# 15_SOLEDNOID.net
KiCad netlist of a schematic drawn in Altium Designer
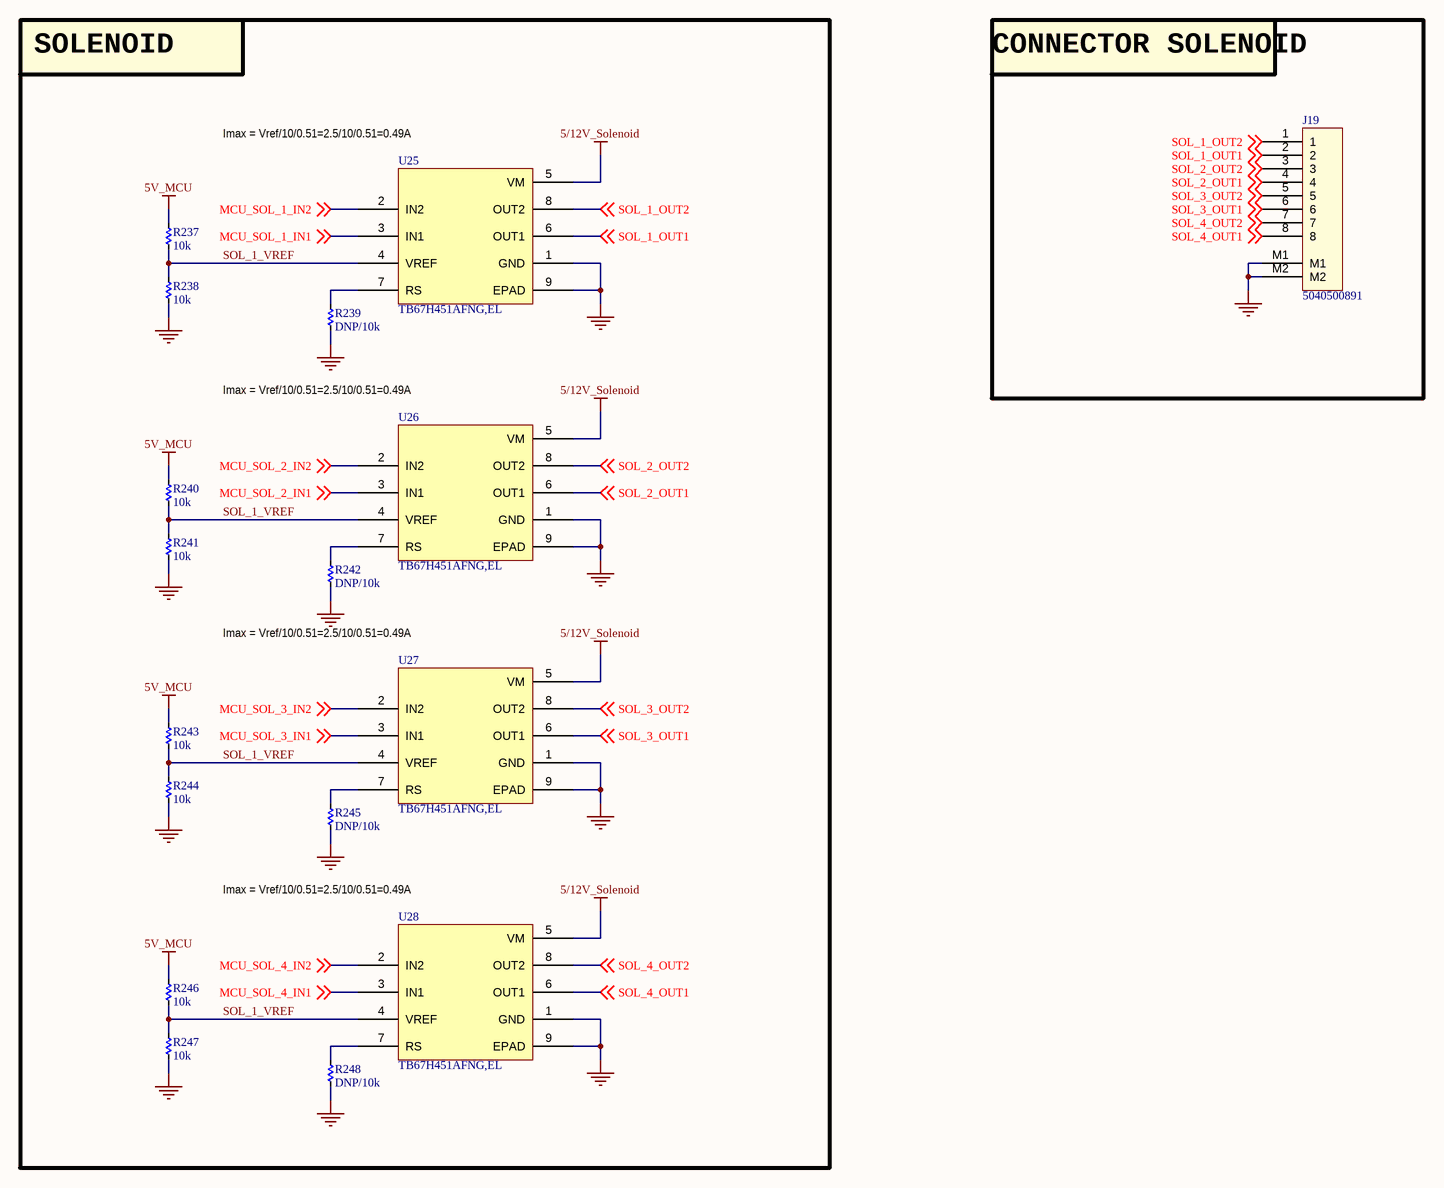
[diagram p0: 15_SOLEDNOID.SchDoc]

(export (version "E")
  (design (tool "Eeschema 10.0.6"))
  (components
    (comp (ref "J19")
      (value "5040500891")
      (footprint "MOLEX_5040500891")
      (libsource (lib "LABLIB") (part "Header 8x1_2M"))
    )
    (comp (ref "R237")
      (value "10k")
      (footprint "RES_C_1005X40")
      (description "RES")
      (libsource (lib "LABLIB") (part "_RES_B_2"))
    )
    (comp (ref "R238")
      (value "10k")
      (footprint "RES_C_1005X40")
      (description "RES")
      (libsource (lib "LABLIB") (part "_RES_B_2"))
    )
    (comp (ref "R239")
      (value "DNP/10k")
      (footprint "RES_C_1005X40")
      (description "RES")
      (libsource (lib "LABLIB") (part "_RES_B_2"))
    )
    (comp (ref "R240")
      (value "10k")
      (footprint "RES_C_1005X40")
      (description "RES")
      (libsource (lib "LABLIB") (part "_RES_B_2"))
    )
    (comp (ref "R241")
      (value "10k")
      (footprint "RES_C_1005X40")
      (description "RES")
      (libsource (lib "LABLIB") (part "_RES_B_2"))
    )
    (comp (ref "R242")
      (value "DNP/10k")
      (footprint "RES_C_1005X40")
      (description "RES")
      (libsource (lib "LABLIB") (part "_RES_B_2"))
    )
    (comp (ref "R243")
      (value "10k")
      (footprint "RES_C_1005X40")
      (description "RES")
      (libsource (lib "LABLIB") (part "_RES_B_2"))
    )
    (comp (ref "R244")
      (value "10k")
      (footprint "RES_C_1005X40")
      (description "RES")
      (libsource (lib "LABLIB") (part "_RES_B_2"))
    )
    (comp (ref "R245")
      (value "DNP/10k")
      (footprint "RES_C_1005X40")
      (description "RES")
      (libsource (lib "LABLIB") (part "_RES_B_2"))
    )
    (comp (ref "R246")
      (value "10k")
      (footprint "RES_C_1005X40")
      (description "RES")
      (libsource (lib "LABLIB") (part "_RES_B_2"))
    )
    (comp (ref "R247")
      (value "10k")
      (footprint "RES_C_1005X40")
      (description "RES")
      (libsource (lib "LABLIB") (part "_RES_B_2"))
    )
    (comp (ref "R248")
      (value "DNP/10k")
      (footprint "RES_C_1005X40")
      (description "RES")
      (libsource (lib "LABLIB") (part "_RES_B_2"))
    )
    (comp (ref "U25")
      (value "TB67H451AFNG,EL")
      (description "BRUSHED MOTOR DRIVER IC, 50V, 3.")
      (libsource (lib "LABLIB") (part "IC_H_bridge_TB67H451AFNG,EL"))
    )
    (comp (ref "U26")
      (value "TB67H451AFNG,EL")
      (description "BRUSHED MOTOR DRIVER IC, 50V, 3.")
      (libsource (lib "LABLIB") (part "IC_H_bridge_TB67H451AFNG,EL"))
    )
    (comp (ref "U27")
      (value "TB67H451AFNG,EL")
      (description "BRUSHED MOTOR DRIVER IC, 50V, 3.")
      (libsource (lib "LABLIB") (part "IC_H_bridge_TB67H451AFNG,EL"))
    )
    (comp (ref "U28")
      (value "TB67H451AFNG,EL")
      (description "BRUSHED MOTOR DRIVER IC, 50V, 3.")
      (libsource (lib "LABLIB") (part "IC_H_bridge_TB67H451AFNG,EL"))
    )
  )
  (nets
    (net (code "1") (name "/SOL_1_VREF") (class "Default")
      (node (ref "R237") (pin "2") (pinfunction "2_2") (pintype "passive"))
      (node (ref "R238") (pin "1") (pinfunction "1_1") (pintype "passive"))
      (node (ref "R240") (pin "2") (pinfunction "2_2") (pintype "passive"))
      (node (ref "R241") (pin "1") (pinfunction "1_1") (pintype "passive"))
      (node (ref "R243") (pin "2") (pinfunction "2_2") (pintype "passive"))
      (node (ref "R244") (pin "1") (pinfunction "1_1") (pintype "passive"))
      (node (ref "R246") (pin "2") (pinfunction "2_2") (pintype "passive"))
      (node (ref "R247") (pin "1") (pinfunction "1_1") (pintype "passive"))
      (node (ref "U25") (pin "4") (pinfunction "VREF_4") (pintype "passive"))
      (node (ref "U26") (pin "4") (pinfunction "VREF_4") (pintype "passive"))
      (node (ref "U27") (pin "4") (pinfunction "VREF_4") (pintype "passive"))
      (node (ref "U28") (pin "4") (pinfunction "VREF_4") (pintype "passive"))
    )
    (net (code "2") (name "5V_MCU") (class "Default")
      (node (ref "R237") (pin "1") (pinfunction "1_1") (pintype "passive"))
      (node (ref "R240") (pin "1") (pinfunction "1_1") (pintype "passive"))
      (node (ref "R243") (pin "1") (pinfunction "1_1") (pintype "passive"))
      (node (ref "R246") (pin "1") (pinfunction "1_1") (pintype "passive"))
    )
    (net (code "3") (name "5{slash}12V_Solenoid") (class "Default")
      (node (ref "U25") (pin "5") (pinfunction "VM_5") (pintype "passive"))
      (node (ref "U26") (pin "5") (pinfunction "VM_5") (pintype "passive"))
      (node (ref "U27") (pin "5") (pinfunction "VM_5") (pintype "passive"))
      (node (ref "U28") (pin "5") (pinfunction "VM_5") (pintype "passive"))
    )
    (net (code "4") (name "GND") (class "Default")
      (node (ref "J19") (pin "M1") (pinfunction "M1_M1") (pintype "passive"))
      (node (ref "J19") (pin "M2") (pinfunction "M2_M2") (pintype "passive"))
      (node (ref "R238") (pin "2") (pinfunction "2_2") (pintype "passive"))
      (node (ref "R239") (pin "2") (pinfunction "2_2") (pintype "passive"))
      (node (ref "R241") (pin "2") (pinfunction "2_2") (pintype "passive"))
      (node (ref "R242") (pin "2") (pinfunction "2_2") (pintype "passive"))
      (node (ref "R244") (pin "2") (pinfunction "2_2") (pintype "passive"))
      (node (ref "R245") (pin "2") (pinfunction "2_2") (pintype "passive"))
      (node (ref "R247") (pin "2") (pinfunction "2_2") (pintype "passive"))
      (node (ref "R248") (pin "2") (pinfunction "2_2") (pintype "passive"))
      (node (ref "U25") (pin "1") (pinfunction "GND_1") (pintype "passive"))
      (node (ref "U25") (pin "9") (pinfunction "EPAD_9") (pintype "passive"))
      (node (ref "U26") (pin "1") (pinfunction "GND_1") (pintype "passive"))
      (node (ref "U26") (pin "9") (pinfunction "EPAD_9") (pintype "passive"))
      (node (ref "U27") (pin "1") (pinfunction "GND_1") (pintype "passive"))
      (node (ref "U27") (pin "9") (pinfunction "EPAD_9") (pintype "passive"))
      (node (ref "U28") (pin "1") (pinfunction "GND_1") (pintype "passive"))
      (node (ref "U28") (pin "9") (pinfunction "EPAD_9") (pintype "passive"))
    )
    (net (code "5") (name "MCU_SOL_1_IN1") (class "Default")
      (node (ref "U25") (pin "3") (pinfunction "IN1_3") (pintype "passive"))
    )
    (net (code "6") (name "MCU_SOL_1_IN2") (class "Default")
      (node (ref "U25") (pin "2") (pinfunction "IN2_2") (pintype "passive"))
    )
    (net (code "7") (name "MCU_SOL_2_IN1") (class "Default")
      (node (ref "U26") (pin "3") (pinfunction "IN1_3") (pintype "passive"))
    )
    (net (code "8") (name "MCU_SOL_2_IN2") (class "Default")
      (node (ref "U26") (pin "2") (pinfunction "IN2_2") (pintype "passive"))
    )
    (net (code "9") (name "MCU_SOL_3_IN1") (class "Default")
      (node (ref "U27") (pin "3") (pinfunction "IN1_3") (pintype "passive"))
    )
    (net (code "10") (name "MCU_SOL_3_IN2") (class "Default")
      (node (ref "U27") (pin "2") (pinfunction "IN2_2") (pintype "passive"))
    )
    (net (code "11") (name "MCU_SOL_4_IN1") (class "Default")
      (node (ref "U28") (pin "3") (pinfunction "IN1_3") (pintype "passive"))
    )
    (net (code "12") (name "MCU_SOL_4_IN2") (class "Default")
      (node (ref "U28") (pin "2") (pinfunction "IN2_2") (pintype "passive"))
    )
    (net (code "13") (name "Net-(U25-RS)") (class "Default")
      (node (ref "R239") (pin "1") (pinfunction "1_1") (pintype "passive"))
      (node (ref "U25") (pin "7") (pinfunction "RS_7") (pintype "passive"))
    )
    (net (code "14") (name "Net-(U26-RS)") (class "Default")
      (node (ref "R242") (pin "1") (pinfunction "1_1") (pintype "passive"))
      (node (ref "U26") (pin "7") (pinfunction "RS_7") (pintype "passive"))
    )
    (net (code "15") (name "Net-(U27-RS)") (class "Default")
      (node (ref "R245") (pin "1") (pinfunction "1_1") (pintype "passive"))
      (node (ref "U27") (pin "7") (pinfunction "RS_7") (pintype "passive"))
    )
    (net (code "16") (name "Net-(U28-RS)") (class "Default")
      (node (ref "R248") (pin "1") (pinfunction "1_1") (pintype "passive"))
      (node (ref "U28") (pin "7") (pinfunction "RS_7") (pintype "passive"))
    )
    (net (code "17") (name "SOL_1_OUT1") (class "Default")
      (node (ref "J19") (pin "2") (pinfunction "2_2") (pintype "passive"))
      (node (ref "U25") (pin "6") (pinfunction "OUT1_6") (pintype "passive"))
    )
    (net (code "18") (name "SOL_1_OUT2") (class "Default")
      (node (ref "J19") (pin "1") (pinfunction "1_1") (pintype "passive"))
      (node (ref "U25") (pin "8") (pinfunction "OUT2_8") (pintype "passive"))
    )
    (net (code "19") (name "SOL_2_OUT1") (class "Default")
      (node (ref "J19") (pin "4") (pinfunction "4_4") (pintype "passive"))
      (node (ref "U26") (pin "6") (pinfunction "OUT1_6") (pintype "passive"))
    )
    (net (code "20") (name "SOL_2_OUT2") (class "Default")
      (node (ref "J19") (pin "3") (pinfunction "3_3") (pintype "passive"))
      (node (ref "U26") (pin "8") (pinfunction "OUT2_8") (pintype "passive"))
    )
    (net (code "21") (name "SOL_3_OUT1") (class "Default")
      (node (ref "J19") (pin "6") (pinfunction "6_6") (pintype "passive"))
      (node (ref "U27") (pin "6") (pinfunction "OUT1_6") (pintype "passive"))
    )
    (net (code "22") (name "SOL_3_OUT2") (class "Default")
      (node (ref "J19") (pin "5") (pinfunction "5_5") (pintype "passive"))
      (node (ref "U27") (pin "8") (pinfunction "OUT2_8") (pintype "passive"))
    )
    (net (code "23") (name "SOL_4_OUT1") (class "Default")
      (node (ref "J19") (pin "8") (pinfunction "8_8") (pintype "passive"))
      (node (ref "U28") (pin "6") (pinfunction "OUT1_6") (pintype "passive"))
    )
    (net (code "24") (name "SOL_4_OUT2") (class "Default")
      (node (ref "J19") (pin "7") (pinfunction "7_7") (pintype "passive"))
      (node (ref "U28") (pin "8") (pinfunction "OUT2_8") (pintype "passive"))
    )
  )
)
